# Humidity.net
KiCad netlist of a schematic drawn in EAGLE
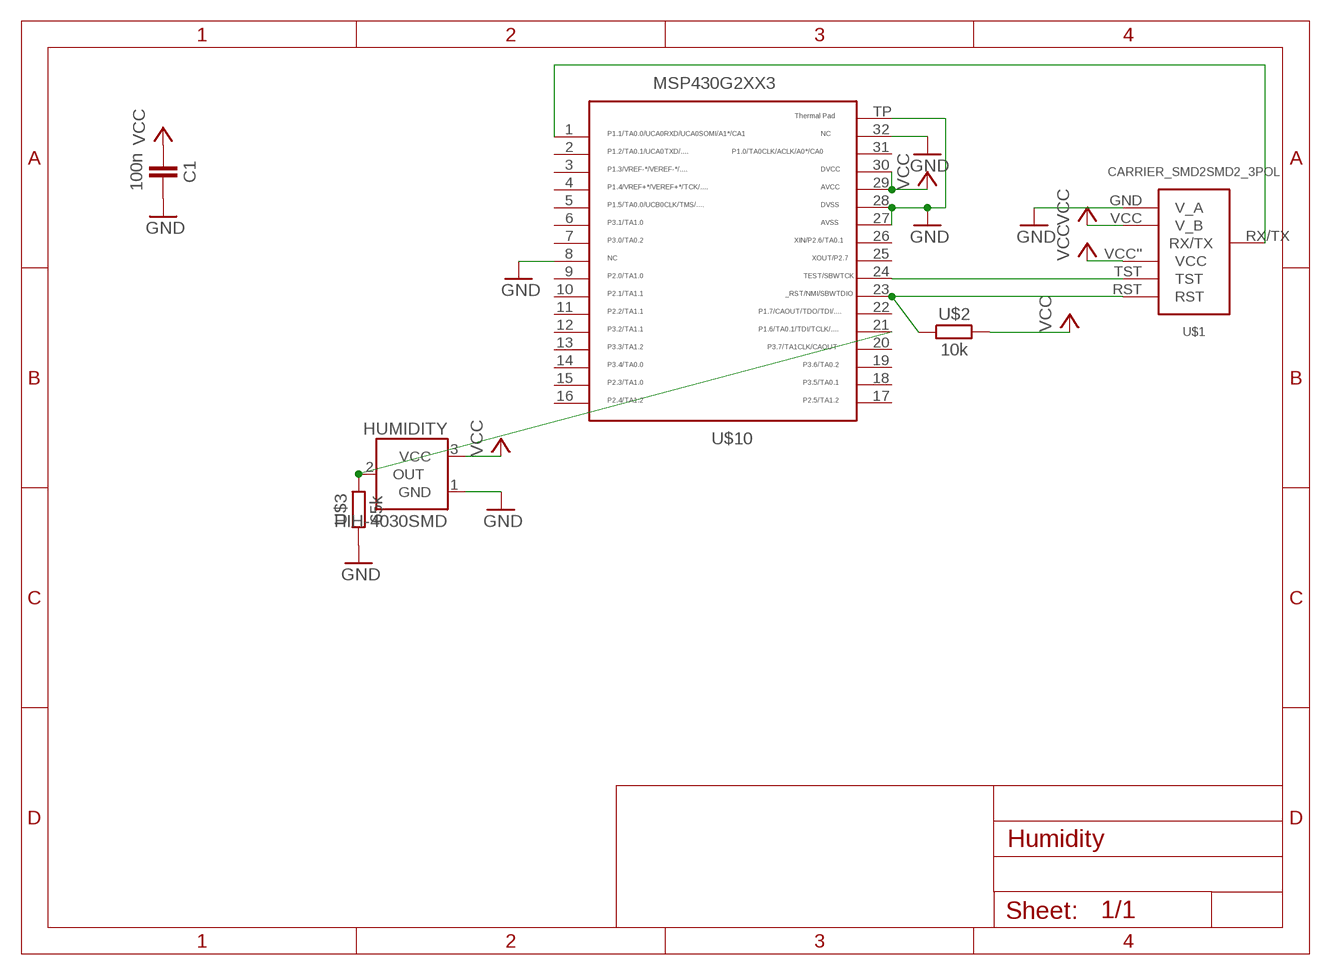
[diagram p0: schematic, sheet 1]

(export (version "E")
  (design (tool "Eeschema 10.0.6"))
  (components
    (comp (ref "C1")
      (value "100n")
      (footprint "eagle-import:603")
      (libsource (lib "eagle-import") (part "CAPACITOR"))
    )
    (comp (ref "HUMIDITY")
      (value "HIH-4030SMD")
      (footprint "eagle-import:HIH-4030")
      (libsource (lib "eagle-import") (part "HIH-4030SMD"))
    )
    (comp (ref "U$1")
      (value "CARRIER_SMD2SMD2_3POL")
      (footprint "eagle-import:CARRIER_SMD2_3POL")
      (libsource (lib "eagle-import") (part "CARRIER_SMD2SMD2_3POL"))
    )
    (comp (ref "U$2")
      (value "10k")
      (footprint "eagle-import:603")
      (libsource (lib "eagle-import") (part "RESISTOR0603"))
    )
    (comp (ref "U$3")
      (value "65k")
      (footprint "eagle-import:603")
      (libsource (lib "eagle-import") (part "RESISTOR0603"))
    )
    (comp (ref "U$10")
      (value "MSP430G2553")
      (footprint "eagle-import:QFN32")
      (libsource (lib "eagle-import") (part "MSP430G2553"))
    )
  )
  (nets
    (net (code "1") (name "GND") (class "Default")
      (node (ref "C1") (pin "2") (pinfunction "2_2") (pintype "passive"))
      (node (ref "HUMIDITY") (pin "1") (pinfunction "GND_1") (pintype "bidirectional"))
      (node (ref "U$1") (pin "GND") (pinfunction "V_A_GND") (pintype "bidirectional"))
      (node (ref "U$10") (pin "27") (pinfunction "27_27") (pintype "bidirectional"))
      (node (ref "U$10") (pin "28") (pinfunction "28_28") (pintype "bidirectional"))
      (node (ref "U$10") (pin "32") (pinfunction "32_32") (pintype "bidirectional"))
      (node (ref "U$10") (pin "8") (pinfunction "8_8") (pintype "bidirectional"))
      (node (ref "U$10") (pin "TP") (pinfunction "TP_TP") (pintype "bidirectional"))
      (node (ref "U$3") (pin "1") (pinfunction "1_1") (pintype "passive"))
    )
    (net (code "2") (name "Net-(HUMIDITY-OUT)") (class "Default")
      (node (ref "HUMIDITY") (pin "2") (pinfunction "OUT_2") (pintype "bidirectional"))
      (node (ref "U$10") (pin "21") (pinfunction "21_21") (pintype "bidirectional"))
      (node (ref "U$3") (pin "2") (pinfunction "2_2") (pintype "passive"))
    )
    (net (code "3") (name "Net-(U$1-PadRST)") (class "Default")
      (node (ref "U$1") (pin "RST") (pinfunction "RST_RST") (pintype "bidirectional"))
      (node (ref "U$10") (pin "23") (pinfunction "23_23") (pintype "bidirectional"))
      (node (ref "U$2") (pin "1") (pinfunction "1_1") (pintype "passive"))
    )
    (net (code "4") (name "Net-(U$1-PadRX{slash}TX)") (class "Default")
      (node (ref "U$1") (pin "RX/TX") (pinfunction "RX/TX_RX/TX") (pintype "bidirectional"))
      (node (ref "U$10") (pin "1") (pinfunction "1_1") (pintype "bidirectional"))
    )
    (net (code "5") (name "Net-(U$1-PadTST)") (class "Default")
      (node (ref "U$1") (pin "TST") (pinfunction "TST_TST") (pintype "bidirectional"))
      (node (ref "U$10") (pin "24") (pinfunction "24_24") (pintype "bidirectional"))
    )
    (net (code "6") (name "VCC") (class "Default")
      (node (ref "C1") (pin "1") (pinfunction "1_1") (pintype "passive"))
      (node (ref "HUMIDITY") (pin "3") (pinfunction "VCC_3") (pintype "bidirectional"))
      (node (ref "U$1") (pin "VCC") (pinfunction "V_B_VCC") (pintype "bidirectional"))
      (node (ref "U$1") (pin "VCC''") (pinfunction "VCC_VCC''") (pintype "bidirectional"))
      (node (ref "U$10") (pin "29") (pinfunction "29_29") (pintype "bidirectional"))
      (node (ref "U$10") (pin "30") (pinfunction "30_30") (pintype "bidirectional"))
      (node (ref "U$2") (pin "2") (pinfunction "2_2") (pintype "passive"))
    )
    (net (code "7") (name "unconnected-(U$10-Pad2)") (class "Default")
      (node (ref "U$10") (pin "2") (pinfunction "2_2") (pintype "bidirectional"))
    )
    (net (code "8") (name "unconnected-(U$10-Pad3)") (class "Default")
      (node (ref "U$10") (pin "3") (pinfunction "3_3") (pintype "bidirectional"))
    )
    (net (code "9") (name "unconnected-(U$10-Pad4)") (class "Default")
      (node (ref "U$10") (pin "4") (pinfunction "4_4") (pintype "bidirectional"))
    )
    (net (code "10") (name "unconnected-(U$10-Pad5)") (class "Default")
      (node (ref "U$10") (pin "5") (pinfunction "5_5") (pintype "bidirectional"))
    )
    (net (code "11") (name "unconnected-(U$10-Pad6)") (class "Default")
      (node (ref "U$10") (pin "6") (pinfunction "6_6") (pintype "bidirectional"))
    )
    (net (code "12") (name "unconnected-(U$10-Pad7)") (class "Default")
      (node (ref "U$10") (pin "7") (pinfunction "7_7") (pintype "bidirectional"))
    )
    (net (code "13") (name "unconnected-(U$10-Pad9)") (class "Default")
      (node (ref "U$10") (pin "9") (pinfunction "9_9") (pintype "bidirectional"))
    )
    (net (code "14") (name "unconnected-(U$10-Pad10)") (class "Default")
      (node (ref "U$10") (pin "10") (pinfunction "10_10") (pintype "bidirectional"))
    )
    (net (code "15") (name "unconnected-(U$10-Pad11)") (class "Default")
      (node (ref "U$10") (pin "11") (pinfunction "11_11") (pintype "bidirectional"))
    )
    (net (code "16") (name "unconnected-(U$10-Pad12)") (class "Default")
      (node (ref "U$10") (pin "12") (pinfunction "12_12") (pintype "bidirectional"))
    )
    (net (code "17") (name "unconnected-(U$10-Pad13)") (class "Default")
      (node (ref "U$10") (pin "13") (pinfunction "13_13") (pintype "bidirectional"))
    )
    (net (code "18") (name "unconnected-(U$10-Pad14)") (class "Default")
      (node (ref "U$10") (pin "14") (pinfunction "14_14") (pintype "bidirectional"))
    )
    (net (code "19") (name "unconnected-(U$10-Pad15)") (class "Default")
      (node (ref "U$10") (pin "15") (pinfunction "15_15") (pintype "bidirectional"))
    )
    (net (code "20") (name "unconnected-(U$10-Pad16)") (class "Default")
      (node (ref "U$10") (pin "16") (pinfunction "16_16") (pintype "bidirectional"))
    )
    (net (code "21") (name "unconnected-(U$10-Pad17)") (class "Default")
      (node (ref "U$10") (pin "17") (pinfunction "17_17") (pintype "bidirectional"))
    )
    (net (code "22") (name "unconnected-(U$10-Pad18)") (class "Default")
      (node (ref "U$10") (pin "18") (pinfunction "18_18") (pintype "bidirectional"))
    )
    (net (code "23") (name "unconnected-(U$10-Pad19)") (class "Default")
      (node (ref "U$10") (pin "19") (pinfunction "19_19") (pintype "bidirectional"))
    )
    (net (code "24") (name "unconnected-(U$10-Pad20)") (class "Default")
      (node (ref "U$10") (pin "20") (pinfunction "20_20") (pintype "bidirectional"))
    )
    (net (code "25") (name "unconnected-(U$10-Pad22)") (class "Default")
      (node (ref "U$10") (pin "22") (pinfunction "22_22") (pintype "bidirectional"))
    )
    (net (code "26") (name "unconnected-(U$10-Pad25)") (class "Default")
      (node (ref "U$10") (pin "25") (pinfunction "25_25") (pintype "bidirectional"))
    )
    (net (code "27") (name "unconnected-(U$10-Pad26)") (class "Default")
      (node (ref "U$10") (pin "26") (pinfunction "26_26") (pintype "bidirectional"))
    )
    (net (code "28") (name "unconnected-(U$10-Pad31)") (class "Default")
      (node (ref "U$10") (pin "31") (pinfunction "31_31") (pintype "bidirectional"))
    )
  )
)
